# ESP_LoRa_Scale_V1_54.net
KiCad netlist of a schematic drawn in EAGLE
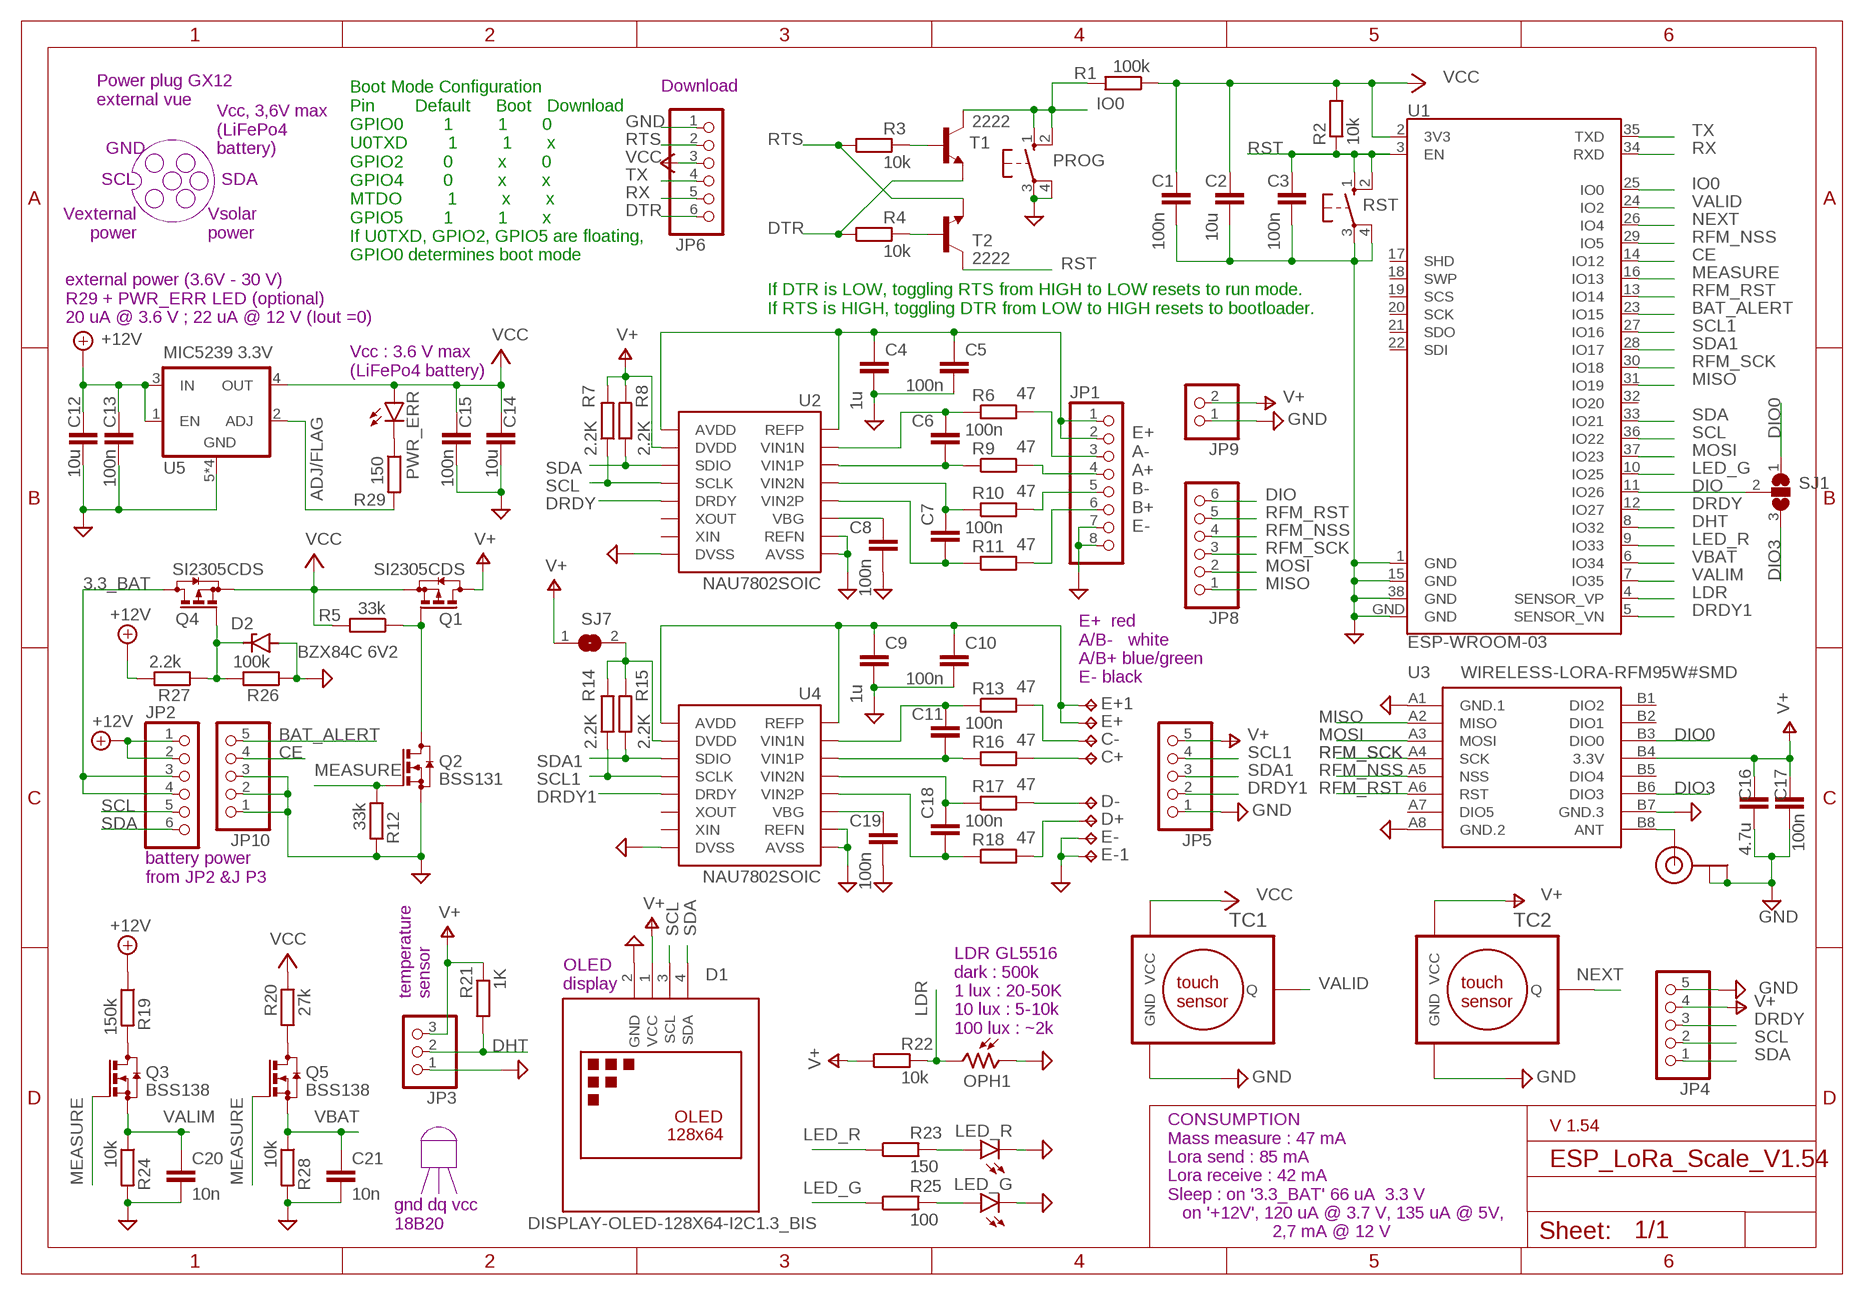
[diagram p0: schematic, sheet 1]

(export (version "E")
  (design (tool "Eeschema 10.0.6"))
  (components
    (comp (ref "C+")
      (value "TPTP17SQ")
      (footprint "eagle-import:TP17SQ")
      (libsource (lib "eagle-import") (part "TPTP17SQ"))
    )
    (comp (ref "C-")
      (value "TPTP17SQ")
      (footprint "eagle-import:TP17SQ")
      (libsource (lib "eagle-import") (part "TPTP17SQ"))
    )
    (comp (ref "C1")
      (value "100n")
      (footprint "eagle-import:C1206")
      (libsource (lib "eagle-import") (part "CC1206"))
    )
    (comp (ref "C2")
      (value "10u")
      (footprint "eagle-import:C1210")
      (libsource (lib "eagle-import") (part "CC1210"))
    )
    (comp (ref "C3")
      (value "100n")
      (footprint "eagle-import:C1206")
      (libsource (lib "eagle-import") (part "CC1206"))
    )
    (comp (ref "C4")
      (value "1u")
      (footprint "eagle-import:C1210")
      (libsource (lib "eagle-import") (part "CC1210"))
    )
    (comp (ref "C5")
      (value "100n")
      (footprint "eagle-import:C1206")
      (libsource (lib "eagle-import") (part "CC1206"))
    )
    (comp (ref "C6")
      (value "100n")
      (footprint "eagle-import:C1206")
      (libsource (lib "eagle-import") (part "CC1206"))
    )
    (comp (ref "C7")
      (value "100n")
      (footprint "eagle-import:C1206")
      (libsource (lib "eagle-import") (part "CC1206"))
    )
    (comp (ref "C8")
      (value "100n")
      (footprint "eagle-import:C1206")
      (libsource (lib "eagle-import") (part "CC1206"))
    )
    (comp (ref "C9")
      (value "1u")
      (footprint "eagle-import:C1210")
      (libsource (lib "eagle-import") (part "CC1210"))
    )
    (comp (ref "C10")
      (value "100n")
      (footprint "eagle-import:C1206")
      (libsource (lib "eagle-import") (part "CC1206"))
    )
    (comp (ref "C11")
      (value "100n")
      (footprint "eagle-import:C1206")
      (libsource (lib "eagle-import") (part "CC1206"))
    )
    (comp (ref "C12")
      (value "10u")
      (footprint "eagle-import:C1210")
      (libsource (lib "eagle-import") (part "CC1210"))
    )
    (comp (ref "C13")
      (value "100n")
      (footprint "eagle-import:C1206")
      (libsource (lib "eagle-import") (part "CC1206"))
    )
    (comp (ref "C14")
      (value "10u")
      (footprint "eagle-import:C1210")
      (libsource (lib "eagle-import") (part "CC1210"))
    )
    (comp (ref "C15")
      (value "100n")
      (footprint "eagle-import:C1206")
      (libsource (lib "eagle-import") (part "CC1206"))
    )
    (comp (ref "C16")
      (value "4.7u")
      (footprint "eagle-import:C1210")
      (libsource (lib "eagle-import") (part "CC1210"))
    )
    (comp (ref "C17")
      (value "100n")
      (footprint "eagle-import:C1206")
      (libsource (lib "eagle-import") (part "CC1206"))
    )
    (comp (ref "C18")
      (value "100n")
      (footprint "eagle-import:C1206")
      (libsource (lib "eagle-import") (part "CC1206"))
    )
    (comp (ref "C19")
      (value "100n")
      (footprint "eagle-import:C1206")
      (libsource (lib "eagle-import") (part "CC1206"))
    )
    (comp (ref "C20")
      (value "10n")
      (footprint "eagle-import:C1206")
      (libsource (lib "eagle-import") (part "CC1206"))
    )
    (comp (ref "C21")
      (value "10n")
      (footprint "eagle-import:C1206")
      (libsource (lib "eagle-import") (part "CC1206"))
    )
    (comp (ref "D+")
      (value "TPTP17SQ")
      (footprint "eagle-import:TP17SQ")
      (libsource (lib "eagle-import") (part "TPTP17SQ"))
    )
    (comp (ref "D-")
      (value "TPTP17SQ")
      (footprint "eagle-import:TP17SQ")
      (libsource (lib "eagle-import") (part "TPTP17SQ"))
    )
    (comp (ref "D1")
      (value "DISPLAY-OLED-128X64-I2C1.3_BIS")
      (footprint "eagle-import:DISPLAY-OLED-128X64-1.3-I2C_BIS")
      (libsource (lib "eagle-import") (part "DISPLAY-OLED-128X64-I2C1.3_BIS"))
    )
    (comp (ref "D2")
      (value "BZX84C 6V2")
      (footprint "eagle-import:TO236")
      (libsource (lib "eagle-import") (part "BZX84CSMD"))
    )
    (comp (ref "E+")
      (value "TPTP17SQ")
      (footprint "eagle-import:TP17SQ")
      (libsource (lib "eagle-import") (part "TPTP17SQ"))
    )
    (comp (ref "E+1")
      (value "TPTP17SQ")
      (footprint "eagle-import:TP17SQ")
      (libsource (lib "eagle-import") (part "TPTP17SQ"))
    )
    (comp (ref "E-")
      (value "TPTP17SQ")
      (footprint "eagle-import:TP17SQ")
      (libsource (lib "eagle-import") (part "TPTP17SQ"))
    )
    (comp (ref "E-1")
      (value "TPTP17SQ")
      (footprint "eagle-import:TP17SQ")
      (libsource (lib "eagle-import") (part "TPTP17SQ"))
    )
    (comp (ref "J1")
      (value "U.FL")
      (footprint "eagle-import:U.FL")
      (libsource (lib "eagle-import") (part "U.FL"))
    )
    (comp (ref "JP1")
      (value "PINHD-1X8")
      (footprint "eagle-import:1X08")
      (libsource (lib "eagle-import") (part "PINHD-1X8"))
    )
    (comp (ref "JP2")
      (value "PINHD-1X6")
      (footprint "eagle-import:1X06")
      (libsource (lib "eagle-import") (part "PINHD-1X6"))
    )
    (comp (ref "JP3")
      (value "PINHD-1X3")
      (footprint "eagle-import:1X03")
      (libsource (lib "eagle-import") (part "PINHD-1X3"))
    )
    (comp (ref "JP4")
      (value "PINHD-1X5")
      (footprint "eagle-import:1X05")
      (libsource (lib "eagle-import") (part "PINHD-1X5"))
    )
    (comp (ref "JP5")
      (value "PINHD-1X5")
      (footprint "eagle-import:1X05")
      (libsource (lib "eagle-import") (part "PINHD-1X5"))
    )
    (comp (ref "JP6")
      (value "PINHD-1X6")
      (footprint "eagle-import:1X06")
      (libsource (lib "eagle-import") (part "PINHD-1X6"))
    )
    (comp (ref "JP8")
      (value "PINHD-1X6")
      (footprint "eagle-import:1X06")
      (libsource (lib "eagle-import") (part "PINHD-1X6"))
    )
    (comp (ref "JP9")
      (value "PINHD-1X2")
      (footprint "eagle-import:1X02")
      (libsource (lib "eagle-import") (part "PINHD-1X2"))
    )
    (comp (ref "JP10")
      (value "PINHD-1X5")
      (footprint "eagle-import:1X05")
      (libsource (lib "eagle-import") (part "PINHD-1X5"))
    )
    (comp (ref "LED_G")
      (value "LEDSMT1206")
      (footprint "eagle-import:1206")
      (libsource (lib "eagle-import") (part "LEDSMT1206"))
    )
    (comp (ref "LED_R")
      (value "LEDSMT1206")
      (footprint "eagle-import:1206")
      (libsource (lib "eagle-import") (part "LEDSMT1206"))
    )
    (comp (ref "OPH1")
      (value "VT93N2")
      (footprint "eagle-import:VT900")
      (libsource (lib "eagle-import") (part "VT93N2"))
    )
    (comp (ref "PROG")
      (value "10-XX")
      (footprint "eagle-import:B3F-10XX")
      (fields (field (name "MPN") "B3F-1000"))
      (libsource (lib "eagle-import") (part "10-XX"))
    )
    (comp (ref "PWR_ERR")
      (value "LEDSMT1206")
      (footprint "eagle-import:1206")
      (libsource (lib "eagle-import") (part "LEDSMT1206"))
    )
    (comp (ref "Q1")
      (value "SI2305CDS")
      (footprint "eagle-import:SOT23")
      (libsource (lib "eagle-import") (part "SI2305CDS"))
    )
    (comp (ref "Q2")
      (value "BSS131")
      (footprint "eagle-import:SOT23")
      (libsource (lib "eagle-import") (part "BSS131"))
    )
    (comp (ref "Q3")
      (value "BSS138")
      (footprint "eagle-import:SOT23")
      (libsource (lib "eagle-import") (part "BSS138"))
    )
    (comp (ref "Q4")
      (value "SI2305CDS")
      (footprint "eagle-import:SOT23")
      (libsource (lib "eagle-import") (part "SI2305CDS"))
    )
    (comp (ref "Q5")
      (value "BSS138")
      (footprint "eagle-import:SOT23")
      (libsource (lib "eagle-import") (part "BSS138"))
    )
    (comp (ref "R1")
      (value "100k")
      (footprint "eagle-import:R1206")
      (libsource (lib "eagle-import") (part "RR1206"))
    )
    (comp (ref "R2")
      (value "10k")
      (footprint "eagle-import:R1206")
      (libsource (lib "eagle-import") (part "RR1206"))
    )
    (comp (ref "R3")
      (value "10k")
      (footprint "eagle-import:R1206")
      (libsource (lib "eagle-import") (part "RR1206"))
    )
    (comp (ref "R4")
      (value "10k")
      (footprint "eagle-import:R1206")
      (libsource (lib "eagle-import") (part "RR1206"))
    )
    (comp (ref "R5")
      (value "33k")
      (footprint "eagle-import:R1206")
      (libsource (lib "eagle-import") (part "RR1206"))
    )
    (comp (ref "R6")
      (value "47")
      (footprint "eagle-import:R1206")
      (libsource (lib "eagle-import") (part "RR1206"))
    )
    (comp (ref "R7")
      (value "2.2K")
      (footprint "eagle-import:R1206")
      (libsource (lib "eagle-import") (part "RR1206"))
    )
    (comp (ref "R8")
      (value "2.2K")
      (footprint "eagle-import:R1206")
      (libsource (lib "eagle-import") (part "RR1206"))
    )
    (comp (ref "R9")
      (value "47")
      (footprint "eagle-import:R1206")
      (libsource (lib "eagle-import") (part "RR1206"))
    )
    (comp (ref "R10")
      (value "47")
      (footprint "eagle-import:R1206")
      (libsource (lib "eagle-import") (part "RR1206"))
    )
    (comp (ref "R11")
      (value "47")
      (footprint "eagle-import:R1206")
      (libsource (lib "eagle-import") (part "RR1206"))
    )
    (comp (ref "R12")
      (value "33k")
      (footprint "eagle-import:R1206")
      (libsource (lib "eagle-import") (part "RR1206"))
    )
    (comp (ref "R13")
      (value "47")
      (footprint "eagle-import:R1206")
      (libsource (lib "eagle-import") (part "RR1206"))
    )
    (comp (ref "R14")
      (value "2.2K")
      (footprint "eagle-import:R1206")
      (libsource (lib "eagle-import") (part "RR1206"))
    )
    (comp (ref "R15")
      (value "2.2K")
      (footprint "eagle-import:R1206")
      (libsource (lib "eagle-import") (part "RR1206"))
    )
    (comp (ref "R16")
      (value "47")
      (footprint "eagle-import:R1206")
      (libsource (lib "eagle-import") (part "RR1206"))
    )
    (comp (ref "R17")
      (value "47")
      (footprint "eagle-import:R1206")
      (libsource (lib "eagle-import") (part "RR1206"))
    )
    (comp (ref "R18")
      (value "47")
      (footprint "eagle-import:R1206")
      (libsource (lib "eagle-import") (part "RR1206"))
    )
    (comp (ref "R19")
      (value "150k")
      (footprint "eagle-import:R1206")
      (libsource (lib "eagle-import") (part "RR1206"))
    )
    (comp (ref "R20")
      (value "27k")
      (footprint "eagle-import:R1206")
      (libsource (lib "eagle-import") (part "RR1206"))
    )
    (comp (ref "R21")
      (value "1K")
      (footprint "eagle-import:R1206")
      (libsource (lib "eagle-import") (part "RR1206"))
    )
    (comp (ref "R22")
      (value "10k")
      (footprint "eagle-import:R1206")
      (libsource (lib "eagle-import") (part "RR1206"))
    )
    (comp (ref "R23")
      (value "150")
      (footprint "eagle-import:R1206")
      (libsource (lib "eagle-import") (part "RR1206"))
    )
    (comp (ref "R24")
      (value "10k")
      (footprint "eagle-import:R1206")
      (libsource (lib "eagle-import") (part "RR1206"))
    )
    (comp (ref "R25")
      (value "100")
      (footprint "eagle-import:R1206")
      (libsource (lib "eagle-import") (part "RR1206"))
    )
    (comp (ref "R26")
      (value "100k")
      (footprint "eagle-import:R1206")
      (libsource (lib "eagle-import") (part "RR1206"))
    )
    (comp (ref "R27")
      (value "2.2k")
      (footprint "eagle-import:R1206")
      (libsource (lib "eagle-import") (part "RR1206"))
    )
    (comp (ref "R28")
      (value "10k")
      (footprint "eagle-import:R1206")
      (libsource (lib "eagle-import") (part "RR1206"))
    )
    (comp (ref "R29")
      (value "150")
      (footprint "eagle-import:R1206")
      (libsource (lib "eagle-import") (part "RR1206"))
    )
    (comp (ref "RST")
      (value "10-XX")
      (footprint "eagle-import:B3F-10XX")
      (fields (field (name "MPN") "B3F-1000"))
      (libsource (lib "eagle-import") (part "10-XX"))
    )
    (comp (ref "SJ1")
      (value "SJ2W")
      (footprint "eagle-import:SJ_2")
      (libsource (lib "eagle-import") (part "SJ2W"))
    )
    (comp (ref "SJ7") (value "SJ") (footprint "eagle-import:SJ") (libsource (lib "eagle-import") (part "SJ")))
    (comp (ref "T1")
      (value "2222")
      (footprint "eagle-import:SOT23-BEC")
      (libsource (lib "eagle-import") (part "-NPN-SOT23-BECMMBT2222ALT1"))
    )
    (comp (ref "T2")
      (value "2222")
      (footprint "eagle-import:SOT23-BEC")
      (libsource (lib "eagle-import") (part "-NPN-SOT23-BECMMBT2222ALT1"))
    )
    (comp (ref "TC1")
      (value "TTP223R_H")
      (footprint "eagle-import:TTP233RED_H")
      (libsource (lib "eagle-import") (part "TTP223R_H"))
    )
    (comp (ref "TC2")
      (value "TTP223R_H")
      (footprint "eagle-import:TTP233RED_H")
      (libsource (lib "eagle-import") (part "TTP223R_H"))
    )
    (comp (ref "U1")
      (value "ESP-WROOM-03")
      (footprint "eagle-import:ESP-WROOM-03")
      (libsource (lib "eagle-import") (part "ESP-WROOM-03"))
    )
    (comp (ref "U2")
      (value "NAU7802SOIC")
      (footprint "eagle-import:SO16")
      (libsource (lib "eagle-import") (part "NAU7802SOIC"))
    )
    (comp (ref "U3")
      (value "WIRELESS-LORA-RFM95W#SMD")
      (footprint "eagle-import:WIRELESS-LORA-RFM95W#SMD")
      (libsource (lib "eagle-import") (part "WIRELESS-LORA-RFM95W#SMD"))
    )
    (comp (ref "U4")
      (value "NAU7802SOIC")
      (footprint "eagle-import:SO16")
      (libsource (lib "eagle-import") (part "NAU7802SOIC"))
    )
    (comp (ref "U5")
      (value "MIC5239 3.3V")
      (footprint "eagle-import:MSOP08")
      (libsource (lib "eagle-import") (part "MIC5239-ADJMM"))
    )
  )
  (nets
    (net (code "1") (name "+12V") (class "Default")
      (node (ref "C12") (pin "1") (pinfunction "1_1") (pintype "passive"))
      (node (ref "C13") (pin "1") (pinfunction "1_1") (pintype "passive"))
      (node (ref "JP2") (pin "1") (pinfunction "1_1") (pintype "passive"))
      (node (ref "JP2") (pin "2") (pinfunction "2_2") (pintype "passive"))
      (node (ref "R19") (pin "1") (pinfunction "1_1") (pintype "passive"))
      (node (ref "R27") (pin "2") (pinfunction "2_2") (pintype "passive"))
      (node (ref "U5") (pin "1") (pinfunction "EN_1") (pintype "input"))
      (node (ref "U5") (pin "3") (pinfunction "IN_3") (pintype "input"))
    )
    (net (code "2") (name "/3.3_BAT") (class "Default")
      (node (ref "JP2") (pin "3") (pinfunction "3_3") (pintype "passive"))
      (node (ref "JP2") (pin "4") (pinfunction "4_4") (pintype "passive"))
      (node (ref "Q4") (pin "3") (pinfunction "D_3") (pintype "passive"))
    )
    (net (code "3") (name "/ADJ{slash}FLAG") (class "Default")
      (node (ref "R29") (pin "2") (pinfunction "2_2") (pintype "passive"))
      (node (ref "U5") (pin "2") (pinfunction "ADJ_2") (pintype "passive"))
    )
    (net (code "4") (name "/BAT_ALERT") (class "Default")
      (node (ref "JP10") (pin "5") (pinfunction "5_5") (pintype "passive"))
      (node (ref "U1") (pin "23") (pinfunction "IO15_23") (pintype "bidirectional"))
    )
    (net (code "5") (name "/CE") (class "Default")
      (node (ref "JP10") (pin "4") (pinfunction "4_4") (pintype "passive"))
      (node (ref "U1") (pin "14") (pinfunction "IO12_14") (pintype "bidirectional"))
    )
    (net (code "6") (name "/DHT") (class "Default")
      (node (ref "JP3") (pin "2") (pinfunction "2_2") (pintype "passive"))
      (node (ref "R21") (pin "1") (pinfunction "1_1") (pintype "passive"))
      (node (ref "U1") (pin "8") (pinfunction "IO32_8") (pintype "bidirectional"))
    )
    (net (code "7") (name "/DIO") (class "Default")
      (node (ref "JP8") (pin "6") (pinfunction "6_6") (pintype "passive"))
      (node (ref "SJ1") (pin "2") (pinfunction "2_2") (pintype "passive"))
      (node (ref "U1") (pin "11") (pinfunction "IO26_11") (pintype "bidirectional"))
    )
    (net (code "8") (name "/DIO0") (class "Default")
      (node (ref "SJ1") (pin "1") (pinfunction "1_1") (pintype "passive"))
      (node (ref "U3") (pin "B3") (pinfunction "DIO0_B3") (pintype "bidirectional"))
    )
    (net (code "9") (name "/DIO3") (class "Default")
      (node (ref "SJ1") (pin "3") (pinfunction "3_3") (pintype "passive"))
      (node (ref "U3") (pin "B6") (pinfunction "DIO3_B6") (pintype "bidirectional"))
    )
    (net (code "10") (name "/DRDY") (class "Default")
      (node (ref "JP4") (pin "3") (pinfunction "3_3") (pintype "passive"))
      (node (ref "U1") (pin "12") (pinfunction "IO27_12") (pintype "bidirectional"))
      (node (ref "U2") (pin "12") (pinfunction "DRDY_12") (pintype "bidirectional"))
    )
    (net (code "11") (name "/DRDY1") (class "Default")
      (node (ref "JP5") (pin "2") (pinfunction "2_2") (pintype "passive"))
      (node (ref "U1") (pin "5") (pinfunction "SENSOR_VN_5") (pintype "bidirectional"))
      (node (ref "U4") (pin "12") (pinfunction "DRDY_12") (pintype "bidirectional"))
    )
    (net (code "12") (name "/DTR") (class "Default")
      (node (ref "JP6") (pin "6") (pinfunction "6_6") (pintype "passive"))
      (node (ref "R4") (pin "1") (pinfunction "1_1") (pintype "passive"))
      (node (ref "T1") (pin "E") (pinfunction "E_E") (pintype "passive"))
    )
    (net (code "13") (name "/IO0") (class "Default")
      (node (ref "PROG") (pin "1") (pinfunction "S_1") (pintype "passive"))
      (node (ref "PROG") (pin "2") (pinfunction "S1_2") (pintype "passive"))
      (node (ref "R1") (pin "2") (pinfunction "2_2") (pintype "passive"))
      (node (ref "T1") (pin "C") (pinfunction "C_C") (pintype "passive"))
      (node (ref "U1") (pin "25") (pinfunction "IO0_25") (pintype "bidirectional"))
    )
    (net (code "14") (name "/LDR") (class "Default")
      (node (ref "OPH1") (pin "2") (pinfunction "2_2") (pintype "passive"))
      (node (ref "R22") (pin "2") (pinfunction "2_2") (pintype "passive"))
      (node (ref "U1") (pin "4") (pinfunction "SENSOR_VP_4") (pintype "bidirectional"))
    )
    (net (code "15") (name "/LED_G") (class "Default")
      (node (ref "R25") (pin "1") (pinfunction "1_1") (pintype "passive"))
      (node (ref "U1") (pin "10") (pinfunction "IO25_10") (pintype "bidirectional"))
    )
    (net (code "16") (name "/LED_R") (class "Default")
      (node (ref "R23") (pin "1") (pinfunction "1_1") (pintype "passive"))
      (node (ref "U1") (pin "9") (pinfunction "IO33_9") (pintype "bidirectional"))
    )
    (net (code "17") (name "/MEASURE") (class "Default")
      (node (ref "Q2") (pin "1") (pinfunction "G_1") (pintype "passive"))
      (node (ref "Q3") (pin "1") (pinfunction "G_1") (pintype "passive"))
      (node (ref "Q5") (pin "1") (pinfunction "G_1") (pintype "passive"))
      (node (ref "R12") (pin "1") (pinfunction "1_1") (pintype "passive"))
      (node (ref "U1") (pin "16") (pinfunction "IO13_16") (pintype "bidirectional"))
    )
    (net (code "18") (name "/MISO") (class "Default")
      (node (ref "JP8") (pin "1") (pinfunction "1_1") (pintype "passive"))
      (node (ref "U1") (pin "31") (pinfunction "IO19_31") (pintype "bidirectional"))
      (node (ref "U3") (pin "A2") (pinfunction "MISO_A2") (pintype "bidirectional"))
    )
    (net (code "19") (name "/MOSI") (class "Default")
      (node (ref "JP8") (pin "2") (pinfunction "2_2") (pintype "passive"))
      (node (ref "U1") (pin "37") (pinfunction "IO23_37") (pintype "bidirectional"))
      (node (ref "U3") (pin "A3") (pinfunction "MOSI_A3") (pintype "bidirectional"))
    )
    (net (code "20") (name "/NEXT") (class "Default")
      (node (ref "TC2") (pin "P$2") (pinfunction "Q_P$2") (pintype "power_in"))
      (node (ref "U1") (pin "26") (pinfunction "IO4_26") (pintype "bidirectional"))
    )
    (net (code "21") (name "/RFM_NSS") (class "Default")
      (node (ref "JP8") (pin "4") (pinfunction "4_4") (pintype "passive"))
      (node (ref "U1") (pin "29") (pinfunction "IO5_29") (pintype "bidirectional"))
      (node (ref "U3") (pin "A5") (pinfunction "NSS_A5") (pintype "bidirectional"))
    )
    (net (code "22") (name "/RFM_RST") (class "Default")
      (node (ref "JP8") (pin "5") (pinfunction "5_5") (pintype "passive"))
      (node (ref "U1") (pin "13") (pinfunction "IO14_13") (pintype "bidirectional"))
      (node (ref "U3") (pin "A6") (pinfunction "RST_A6") (pintype "bidirectional"))
    )
    (net (code "23") (name "/RFM_SCK") (class "Default")
      (node (ref "JP8") (pin "3") (pinfunction "3_3") (pintype "passive"))
      (node (ref "U1") (pin "30") (pinfunction "IO18_30") (pintype "bidirectional"))
      (node (ref "U3") (pin "A4") (pinfunction "SCK_A4") (pintype "bidirectional"))
    )
    (net (code "24") (name "/RST") (class "Default")
      (node (ref "C3") (pin "1") (pinfunction "1_1") (pintype "passive"))
      (node (ref "R2") (pin "1") (pinfunction "1_1") (pintype "passive"))
      (node (ref "RST") (pin "1") (pinfunction "S_1") (pintype "passive"))
      (node (ref "RST") (pin "2") (pinfunction "S1_2") (pintype "passive"))
      (node (ref "T2") (pin "C") (pinfunction "C_C") (pintype "passive"))
      (node (ref "U1") (pin "3") (pinfunction "EN_3") (pintype "bidirectional"))
    )
    (net (code "25") (name "/RTS") (class "Default")
      (node (ref "JP6") (pin "2") (pinfunction "2_2") (pintype "passive"))
      (node (ref "R3") (pin "1") (pinfunction "1_1") (pintype "passive"))
      (node (ref "T2") (pin "E") (pinfunction "E_E") (pintype "passive"))
    )
    (net (code "26") (name "/RX") (class "Default")
      (node (ref "JP6") (pin "5") (pinfunction "5_5") (pintype "passive"))
      (node (ref "U1") (pin "34") (pinfunction "RXD_34") (pintype "bidirectional"))
    )
    (net (code "27") (name "/SCL") (class "Default")
      (node (ref "D1") (pin "3") (pinfunction "SCL_3") (pintype "bidirectional"))
      (node (ref "JP2") (pin "5") (pinfunction "5_5") (pintype "passive"))
      (node (ref "JP4") (pin "2") (pinfunction "2_2") (pintype "passive"))
      (node (ref "R7") (pin "1") (pinfunction "1_1") (pintype "passive"))
      (node (ref "U1") (pin "36") (pinfunction "IO22_36") (pintype "bidirectional"))
      (node (ref "U2") (pin "13") (pinfunction "SCLK_13") (pintype "bidirectional"))
    )
    (net (code "28") (name "/SCL1") (class "Default")
      (node (ref "JP5") (pin "4") (pinfunction "4_4") (pintype "passive"))
      (node (ref "R14") (pin "1") (pinfunction "1_1") (pintype "passive"))
      (node (ref "U1") (pin "27") (pinfunction "IO16_27") (pintype "bidirectional"))
      (node (ref "U4") (pin "13") (pinfunction "SCLK_13") (pintype "bidirectional"))
    )
    (net (code "29") (name "/SDA") (class "Default")
      (node (ref "D1") (pin "4") (pinfunction "SDA_4") (pintype "bidirectional"))
      (node (ref "JP2") (pin "6") (pinfunction "6_6") (pintype "passive"))
      (node (ref "JP4") (pin "1") (pinfunction "1_1") (pintype "passive"))
      (node (ref "R8") (pin "1") (pinfunction "1_1") (pintype "passive"))
      (node (ref "U1") (pin "33") (pinfunction "IO21_33") (pintype "bidirectional"))
      (node (ref "U2") (pin "14") (pinfunction "SDIO_14") (pintype "bidirectional"))
    )
    (net (code "30") (name "/SDA1") (class "Default")
      (node (ref "JP5") (pin "3") (pinfunction "3_3") (pintype "passive"))
      (node (ref "R15") (pin "1") (pinfunction "1_1") (pintype "passive"))
      (node (ref "U1") (pin "28") (pinfunction "IO17_28") (pintype "bidirectional"))
      (node (ref "U4") (pin "14") (pinfunction "SDIO_14") (pintype "bidirectional"))
    )
    (net (code "31") (name "/TX") (class "Default")
      (node (ref "JP6") (pin "4") (pinfunction "4_4") (pintype "passive"))
      (node (ref "U1") (pin "35") (pinfunction "TXD_35") (pintype "bidirectional"))
    )
    (net (code "32") (name "/VALID") (class "Default")
      (node (ref "TC1") (pin "P$2") (pinfunction "Q_P$2") (pintype "power_in"))
      (node (ref "U1") (pin "24") (pinfunction "IO2_24") (pintype "bidirectional"))
    )
    (net (code "33") (name "/VALIM") (class "Default")
      (node (ref "C20") (pin "1") (pinfunction "1_1") (pintype "passive"))
      (node (ref "Q3") (pin "2") (pinfunction "S_2") (pintype "passive"))
      (node (ref "R24") (pin "1") (pinfunction "1_1") (pintype "passive"))
      (node (ref "U1") (pin "7") (pinfunction "IO35_7") (pintype "bidirectional"))
    )
    (net (code "34") (name "/VBAT") (class "Default")
      (node (ref "C21") (pin "1") (pinfunction "1_1") (pintype "passive"))
      (node (ref "Q5") (pin "2") (pinfunction "S_2") (pintype "passive"))
      (node (ref "R28") (pin "1") (pinfunction "1_1") (pintype "passive"))
      (node (ref "U1") (pin "6") (pinfunction "IO34_6") (pintype "bidirectional"))
    )
    (net (code "35") (name "GND") (class "Default")
      (node (ref "C1") (pin "2") (pinfunction "2_2") (pintype "passive"))
      (node (ref "C10") (pin "2") (pinfunction "2_2") (pintype "passive"))
      (node (ref "C12") (pin "2") (pinfunction "2_2") (pintype "passive"))
      (node (ref "C13") (pin "2") (pinfunction "2_2") (pintype "passive"))
      (node (ref "C14") (pin "2") (pinfunction "2_2") (pintype "passive"))
      (node (ref "C15") (pin "2") (pinfunction "2_2") (pintype "passive"))
      (node (ref "C16") (pin "2") (pinfunction "2_2") (pintype "passive"))
      (node (ref "C17") (pin "2") (pinfunction "2_2") (pintype "passive"))
      (node (ref "C19") (pin "2") (pinfunction "2_2") (pintype "passive"))
      (node (ref "C2") (pin "2") (pinfunction "2_2") (pintype "passive"))
      (node (ref "C20") (pin "2") (pinfunction "2_2") (pintype "passive"))
      (node (ref "C21") (pin "2") (pinfunction "2_2") (pintype "passive"))
      (node (ref "C3") (pin "2") (pinfunction "2_2") (pintype "passive"))
      (node (ref "C4") (pin "2") (pinfunction "2_2") (pintype "passive"))
      (node (ref "C5") (pin "2") (pinfunction "2_2") (pintype "passive"))
      (node (ref "C8") (pin "2") (pinfunction "2_2") (pintype "passive"))
      (node (ref "C9") (pin "2") (pinfunction "2_2") (pintype "passive"))
      (node (ref "D1") (pin "2") (pinfunction "GND_2") (pintype "power_in"))
      (node (ref "D2") (pin "A") (pinfunction "A_A") (pintype "passive"))
      (node (ref "E-") (pin "TP") (pinfunction "TP_TP") (pintype "input"))
      (node (ref "E-1") (pin "TP") (pinfunction "TP_TP") (pintype "input"))
      (node (ref "J1") (pin "1") (pinfunction "GND_1") (pintype "passive"))
      (node (ref "J1") (pin "2") (pinfunction "GND_2") (pintype "passive"))
      (node (ref "JP1") (pin "7") (pinfunction "7_7") (pintype "passive"))
      (node (ref "JP1") (pin "8") (pinfunction "8_8") (pintype "passive"))
      (node (ref "JP10") (pin "1") (pinfunction "1_1") (pintype "passive"))
      (node (ref "JP10") (pin "2") (pinfunction "2_2") (pintype "passive"))
      (node (ref "JP10") (pin "3") (pinfunction "3_3") (pintype "passive"))
      (node (ref "JP3") (pin "1") (pinfunction "1_1") (pintype "passive"))
      (node (ref "JP4") (pin "5") (pinfunction "5_5") (pintype "passive"))
      (node (ref "JP5") (pin "1") (pinfunction "1_1") (pintype "passive"))
      (node (ref "JP6") (pin "1") (pinfunction "1_1") (pintype "passive"))
      (node (ref "JP9") (pin "1") (pinfunction "1_1") (pintype "passive"))
      (node (ref "LED_G") (pin "C") (pinfunction "C_C") (pintype "passive"))
      (node (ref "LED_R") (pin "C") (pinfunction "C_C") (pintype "passive"))
      (node (ref "OPH1") (pin "1") (pinfunction "1_1") (pintype "passive"))
      (node (ref "PROG") (pin "3") (pinfunction "P_3") (pintype "passive"))
      (node (ref "PROG") (pin "4") (pinfunction "P1_4") (pintype "passive"))
      (node (ref "Q2") (pin "2") (pinfunction "S_2") (pintype "passive"))
      (node (ref "R12") (pin "2") (pinfunction "2_2") (pintype "passive"))
      (node (ref "R24") (pin "2") (pinfunction "2_2") (pintype "passive"))
      (node (ref "R26") (pin "1") (pinfunction "1_1") (pintype "passive"))
      (node (ref "R28") (pin "2") (pinfunction "2_2") (pintype "passive"))
      (node (ref "RST") (pin "3") (pinfunction "P_3") (pintype "passive"))
      (node (ref "RST") (pin "4") (pinfunction "P1_4") (pintype "passive"))
      (node (ref "TC1") (pin "P$3") (pinfunction "GND_P$3") (pintype "power_in"))
      (node (ref "TC2") (pin "P$3") (pinfunction "GND_P$3") (pintype "power_in"))
      (node (ref "U1") (pin "1") (pinfunction "GND_1") (pintype "bidirectional"))
      (node (ref "U1") (pin "15") (pinfunction "GND_15") (pintype "bidirectional"))
      (node (ref "U1") (pin "38") (pinfunction "GND_38") (pintype "bidirectional"))
      (node (ref "U1") (pin "GND") (pinfunction "GND_GND") (pintype "bidirectional"))
      (node (ref "U2") (pin "7") (pinfunction "REFN_7") (pintype "bidirectional"))
      (node (ref "U2") (pin "8") (pinfunction "AVSS_8") (pintype "bidirectional"))
      (node (ref "U2") (pin "9") (pinfunction "DVSS_9") (pintype "bidirectional"))
      (node (ref "U3") (pin "A1") (pinfunction "GND.1_A1") (pintype "power_in"))
      (node (ref "U3") (pin "A8") (pinfunction "GND.2_A8") (pintype "power_in"))
      (node (ref "U3") (pin "B7") (pinfunction "GND.3_B7") (pintype "power_in"))
      (node (ref "U4") (pin "7") (pinfunction "REFN_7") (pintype "bidirectional"))
      (node (ref "U4") (pin "8") (pinfunction "AVSS_8") (pintype "bidirectional"))
      (node (ref "U4") (pin "9") (pinfunction "DVSS_9") (pintype "bidirectional"))
      (node (ref "U5") (pin "5") (pinfunction "GND_5") (pintype "power_in"))
      (node (ref "U5") (pin "6") (pinfunction "GND_6") (pintype "power_in"))
      (node (ref "U5") (pin "7") (pinfunction "GND_7") (pintype "power_in"))
      (node (ref "U5") (pin "8") (pinfunction "GND_8") (pintype "power_in"))
    )
    (net (code "36") (name "Net-(C+-PadTP)") (class "Default")
      (node (ref "C+") (pin "TP") (pinfunction "TP_TP") (pintype "input"))
      (node (ref "R16") (pin "2") (pinfunction "2_2") (pintype "passive"))
    )
    (net (code "37") (name "Net-(C--PadTP)") (class "Default")
      (node (ref "C-") (pin "TP") (pinfunction "TP_TP") (pintype "input"))
      (node (ref "R13") (pin "2") (pinfunction "2_2") (pintype "passive"))
    )
    (net (code "38") (name "Net-(D+-PadTP)") (class "Default")
      (node (ref "D+") (pin "TP") (pinfunction "TP_TP") (pintype "input"))
      (node (ref "R18") (pin "2") (pinfunction "2_2") (pintype "passive"))
    )
    (net (code "39") (name "Net-(D--PadTP)") (class "Default")
      (node (ref "D-") (pin "TP") (pinfunction "TP_TP") (pintype "input"))
      (node (ref "R17") (pin "2") (pinfunction "2_2") (pintype "passive"))
    )
    (net (code "40") (name "Net-(J1-SIGNAL)") (class "Default")
      (node (ref "J1") (pin "3") (pinfunction "SIGNAL_3") (pintype "passive"))
      (node (ref "U3") (pin "B8") (pinfunction "ANT_B8") (pintype "passive"))
    )
    (net (code "41") (name "Net-(JP1-Pad3)") (class "Default")
      (node (ref "JP1") (pin "3") (pinfunction "3_3") (pintype "passive"))
      (node (ref "R6") (pin "2") (pinfunction "2_2") (pintype "passive"))
    )
    (net (code "42") (name "Net-(JP1-Pad4)") (class "Default")
      (node (ref "JP1") (pin "4") (pinfunction "4_4") (pintype "passive"))
      (node (ref "R9") (pin "2") (pinfunction "2_2") (pintype "passive"))
    )
    (net (code "43") (name "Net-(JP1-Pad5)") (class "Default")
      (node (ref "JP1") (pin "5") (pinfunction "5_5") (pintype "passive"))
      (node (ref "R10") (pin "2") (pinfunction "2_2") (pintype "passive"))
    )
    (net (code "44") (name "Net-(JP1-Pad6)") (class "Default")
      (node (ref "JP1") (pin "6") (pinfunction "6_6") (pintype "passive"))
      (node (ref "R11") (pin "2") (pinfunction "2_2") (pintype "passive"))
    )
    (net (code "45") (name "Net-(LED_G-PadA)") (class "Default")
      (node (ref "LED_G") (pin "A") (pinfunction "A_A") (pintype "passive"))
      (node (ref "R25") (pin "2") (pinfunction "2_2") (pintype "passive"))
    )
    (net (code "46") (name "Net-(LED_R-PadA)") (class "Default")
      (node (ref "LED_R") (pin "A") (pinfunction "A_A") (pintype "passive"))
      (node (ref "R23") (pin "2") (pinfunction "2_2") (pintype "passive"))
    )
    (net (code "47") (name "Net-(PWR_ERR-PadC)") (class "Default")
      (node (ref "PWR_ERR") (pin "C") (pinfunction "C_C") (pintype "passive"))
      (node (ref "R29") (pin "1") (pinfunction "1_1") (pintype "passive"))
    )
    (net (code "48") (name "Net-(Q1-G)") (class "Default")
      (node (ref "Q1") (pin "1") (pinfunction "G_1") (pintype "passive"))
      (node (ref "Q2") (pin "3") (pinfunction "D_3") (pintype "passive"))
      (node (ref "R5") (pin "1") (pinfunction "1_1") (pintype "passive"))
    )
    (net (code "49") (name "Net-(Q3-D)") (class "Default")
      (node (ref "Q3") (pin "3") (pinfunction "D_3") (pintype "passive"))
      (node (ref "R19") (pin "2") (pinfunction "2_2") (pintype "passive"))
    )
    (net (code "50") (name "Net-(Q4-G)") (class "Default")
      (node (ref "D2") (pin "C") (pinfunction "C_C") (pintype "passive"))
      (node (ref "Q4") (pin "1") (pinfunction "G_1") (pintype "passive"))
      (node (ref "R26") (pin "2") (pinfunction "2_2") (pintype "passive"))
      (node (ref "R27") (pin "1") (pinfunction "1_1") (pintype "passive"))
    )
    (net (code "51") (name "Net-(Q5-D)") (class "Default")
      (node (ref "Q5") (pin "3") (pinfunction "D_3") (pintype "passive"))
      (node (ref "R20") (pin "1") (pinfunction "1_1") (pintype "passive"))
    )
    (net (code "52") (name "Net-(R3-Pad2)") (class "Default")
      (node (ref "R3") (pin "2") (pinfunction "2_2") (pintype "passive"))
      (node (ref "T1") (pin "B") (pinfunction "B_B") (pintype "passive"))
    )
    (net (code "53") (name "Net-(R4-Pad2)") (class "Default")
      (node (ref "R4") (pin "2") (pinfunction "2_2") (pintype "passive"))
      (node (ref "T2") (pin "B") (pinfunction "B_B") (pintype "passive"))
    )
    (net (code "54") (name "Net-(U2-AVDD)") (class "Default")
      (node (ref "C4") (pin "1") (pinfunction "1_1") (pintype "passive"))
      (node (ref "C5") (pin "1") (pinfunction "1_1") (pintype "passive"))
      (node (ref "JP1") (pin "1") (pinfunction "1_1") (pintype "passive"))
      (node (ref "JP1") (pin "2") (pinfunction "2_2") (pintype "passive"))
      (node (ref "U2") (pin "1") (pinfunction "REFP_1") (pintype "bidirectional"))
      (node (ref "U2") (pin "16") (pinfunction "AVDD_16") (pintype "bidirectional"))
    )
    (net (code "55") (name "Net-(U2-VBG)") (class "Default")
      (node (ref "C8") (pin "1") (pinfunction "1_1") (pintype "passive"))
      (node (ref "U2") (pin "6") (pinfunction "VBG_6") (pintype "bidirectional"))
    )
    (net (code "56") (name "Net-(U2-VIN1N)") (class "Default")
      (node (ref "C6") (pin "1") (pinfunction "1_1") (pintype "passive"))
      (node (ref "R6") (pin "1") (pinfunction "1_1") (pintype "passive"))
      (node (ref "U2") (pin "2") (pinfunction "VIN1N_2") (pintype "bidirectional"))
    )
    (net (code "57") (name "Net-(U2-VIN1P)") (class "Default")
      (node (ref "C6") (pin "2") (pinfunction "2_2") (pintype "passive"))
      (node (ref "R9") (pin "1") (pinfunction "1_1") (pintype "passive"))
      (node (ref "U2") (pin "3") (pinfunction "VIN1P_3") (pintype "bidirectional"))
    )
    (net (code "58") (name "Net-(U2-VIN2N)") (class "Default")
      (node (ref "C7") (pin "1") (pinfunction "1_1") (pintype "passive"))
      (node (ref "R10") (pin "1") (pinfunction "1_1") (pintype "passive"))
      (node (ref "U2") (pin "4") (pinfunction "VIN2N_4") (pintype "bidirectional"))
    )
    (net (code "59") (name "Net-(U2-VIN2P)") (class "Default")
      (node (ref "C7") (pin "2") (pinfunction "2_2") (pintype "passive"))
      (node (ref "R11") (pin "1") (pinfunction "1_1") (pintype "passive"))
      (node (ref "U2") (pin "5") (pinfunction "VIN2P_5") (pintype "bidirectional"))
    )
    (net (code "60") (name "Net-(U4-AVDD)") (class "Default")
      (node (ref "C10") (pin "1") (pinfunction "1_1") (pintype "passive"))
      (node (ref "C9") (pin "1") (pinfunction "1_1") (pintype "passive"))
      (node (ref "E+") (pin "TP") (pinfunction "TP_TP") (pintype "input"))
      (node (ref "E+1") (pin "TP") (pinfunction "TP_TP") (pintype "input"))
      (node (ref "U4") (pin "1") (pinfunction "REFP_1") (pintype "bidirectional"))
      (node (ref "U4") (pin "16") (pinfunction "AVDD_16") (pintype "bidirectional"))
    )
    (net (code "61") (name "Net-(U4-DVDD)") (class "Default")
      (node (ref "R14") (pin "2") (pinfunction "2_2") (pintype "passive"))
      (node (ref "R15") (pin "2") (pinfunction "2_2") (pintype "passive"))
      (node (ref "SJ7") (pin "2") (pinfunction "2_2") (pintype "passive"))
      (node (ref "U4") (pin "15") (pinfunction "DVDD_15") (pintype "bidirectional"))
    )
    (net (code "62") (name "Net-(U4-VBG)") (class "Default")
      (node (ref "C19") (pin "1") (pinfunction "1_1") (pintype "passive"))
      (node (ref "U4") (pin "6") (pinfunction "VBG_6") (pintype "bidirectional"))
    )
    (net (code "63") (name "Net-(U4-VIN1N)") (class "Default")
      (node (ref "C11") (pin "1") (pinfunction "1_1") (pintype "passive"))
      (node (ref "R13") (pin "1") (pinfunction "1_1") (pintype "passive"))
      (node (ref "U4") (pin "2") (pinfunction "VIN1N_2") (pintype "bidirectional"))
    )
    (net (code "64") (name "Net-(U4-VIN1P)") (class "Default")
      (node (ref "C11") (pin "2") (pinfunction "2_2") (pintype "passive"))
      (node (ref "R16") (pin "1") (pinfunction "1_1") (pintype "passive"))
      (node (ref "U4") (pin "3") (pinfunction "VIN1P_3") (pintype "bidirectional"))
    )
    (net (code "65") (name "Net-(U4-VIN2N)") (class "Default")
      (node (ref "C18") (pin "1") (pinfunction "1_1") (pintype "passive"))
      (node (ref "R17") (pin "1") (pinfunction "1_1") (pintype "passive"))
      (node (ref "U4") (pin "4") (pinfunction "VIN2N_4") (pintype "bidirectional"))
    )
    (net (code "66") (name "Net-(U4-VIN2P)") (class "Default")
      (node (ref "C18") (pin "2") (pinfunction "2_2") (pintype "passive"))
      (node (ref "R18") (pin "1") (pinfunction "1_1") (pintype "passive"))
      (node (ref "U4") (pin "5") (pinfunction "VIN2P_5") (pintype "bidirectional"))
    )
    (net (code "67") (name "V+") (class "Default")
      (node (ref "C16") (pin "1") (pinfunction "1_1") (pintype "passive"))
      (node (ref "C17") (pin "1") (pinfunction "1_1") (pintype "passive"))
      (node (ref "D1") (pin "1") (pinfunction "VCC_1") (pintype "power_in"))
      (node (ref "JP3") (pin "3") (pinfunction "3_3") (pintype "passive"))
      (node (ref "JP4") (pin "4") (pinfunction "4_4") (pintype "passive"))
      (node (ref "JP5") (pin "5") (pinfunction "5_5") (pintype "passive"))
      (node (ref "JP9") (pin "2") (pinfunction "2_2") (pintype "passive"))
      (node (ref "Q1") (pin "3") (pinfunction "D_3") (pintype "passive"))
      (node (ref "R21") (pin "2") (pinfunction "2_2") (pintype "passive"))
      (node (ref "R22") (pin "1") (pinfunction "1_1") (pintype "passive"))
      (node (ref "R7") (pin "2") (pinfunction "2_2") (pintype "passive"))
      (node (ref "R8") (pin "2") (pinfunction "2_2") (pintype "passive"))
      (node (ref "SJ7") (pin "1") (pinfunction "1_1") (pintype "passive"))
      (node (ref "TC2") (pin "P$1") (pinfunction "VCC_P$1") (pintype "power_in"))
      (node (ref "U2") (pin "15") (pinfunction "DVDD_15") (pintype "bidirectional"))
      (node (ref "U3") (pin "B4") (pinfunction "3.3V_B4") (pintype "power_in"))
    )
    (net (code "68") (name "VCC") (class "Default")
      (node (ref "C1") (pin "1") (pinfunction "1_1") (pintype "passive"))
      (node (ref "C14") (pin "1") (pinfunction "1_1") (pintype "passive"))
      (node (ref "C15") (pin "1") (pinfunction "1_1") (pintype "passive"))
      (node (ref "C2") (pin "1") (pinfunction "1_1") (pintype "passive"))
      (node (ref "JP6") (pin "3") (pinfunction "3_3") (pintype "passive"))
      (node (ref "PWR_ERR") (pin "A") (pinfunction "A_A") (pintype "passive"))
      (node (ref "Q1") (pin "2") (pinfunction "S_2") (pintype "passive"))
      (node (ref "Q4") (pin "2") (pinfunction "S_2") (pintype "passive"))
      (node (ref "R1") (pin "1") (pinfunction "1_1") (pintype "passive"))
      (node (ref "R2") (pin "2") (pinfunction "2_2") (pintype "passive"))
      (node (ref "R20") (pin "2") (pinfunction "2_2") (pintype "passive"))
      (node (ref "R5") (pin "2") (pinfunction "2_2") (pintype "passive"))
      (node (ref "TC1") (pin "P$1") (pinfunction "VCC_P$1") (pintype "power_in"))
      (node (ref "U1") (pin "2") (pinfunction "3V3_2") (pintype "bidirectional"))
      (node (ref "U5") (pin "4") (pinfunction "OUT_4") (pintype "passive"))
    )
    (net (code "69") (name "unconnected-(U1-IO20-Pad32)") (class "Default")
      (node (ref "U1") (pin "32") (pinfunction "IO20_32") (pintype "bidirectional"))
    )
    (net (code "70") (name "unconnected-(U1-SCK-Pad20)") (class "Default")
      (node (ref "U1") (pin "20") (pinfunction "SCK_20") (pintype "bidirectional"))
    )
    (net (code "71") (name "unconnected-(U1-SCS-Pad19)") (class "Default")
      (node (ref "U1") (pin "19") (pinfunction "SCS_19") (pintype "bidirectional"))
    )
    (net (code "72") (name "unconnected-(U1-SDI-Pad22)") (class "Default")
      (node (ref "U1") (pin "22") (pinfunction "SDI_22") (pintype "bidirectional"))
    )
    (net (code "73") (name "unconnected-(U1-SDO-Pad21)") (class "Default")
      (node (ref "U1") (pin "21") (pinfunction "SDO_21") (pintype "bidirectional"))
    )
    (net (code "74") (name "unconnected-(U1-SHD-Pad17)") (class "Default")
      (node (ref "U1") (pin "17") (pinfunction "SHD_17") (pintype "bidirectional"))
    )
    (net (code "75") (name "unconnected-(U1-SWP-Pad18)") (class "Default")
      (node (ref "U1") (pin "18") (pinfunction "SWP_18") (pintype "bidirectional"))
    )
    (net (code "76") (name "unconnected-(U2-XIN-Pad10)") (class "Default")
      (node (ref "U2") (pin "10") (pinfunction "XIN_10") (pintype "bidirectional"))
    )
    (net (code "77") (name "unconnected-(U2-XOUT-Pad11)") (class "Default")
      (node (ref "U2") (pin "11") (pinfunction "XOUT_11") (pintype "bidirectional"))
    )
    (net (code "78") (name "unconnected-(U3-DIO1-PadB2)") (class "Default")
      (node (ref "U3") (pin "B2") (pinfunction "DIO1_B2") (pintype "bidirectional"))
    )
    (net (code "79") (name "unconnected-(U3-DIO2-PadB1)") (class "Default")
      (node (ref "U3") (pin "B1") (pinfunction "DIO2_B1") (pintype "bidirectional"))
    )
    (net (code "80") (name "unconnected-(U3-DIO4-PadB5)") (class "Default")
      (node (ref "U3") (pin "B5") (pinfunction "DIO4_B5") (pintype "bidirectional"))
    )
    (net (code "81") (name "unconnected-(U3-DIO5-PadA7)") (class "Default")
      (node (ref "U3") (pin "A7") (pinfunction "DIO5_A7") (pintype "bidirectional"))
    )
    (net (code "82") (name "unconnected-(U4-XIN-Pad10)") (class "Default")
      (node (ref "U4") (pin "10") (pinfunction "XIN_10") (pintype "bidirectional"))
    )
    (net (code "83") (name "unconnected-(U4-XOUT-Pad11)") (class "Default")
      (node (ref "U4") (pin "11") (pinfunction "XOUT_11") (pintype "bidirectional"))
    )
  )
)
